# controll.net
KiCad netlist of a schematic drawn in EAGLE
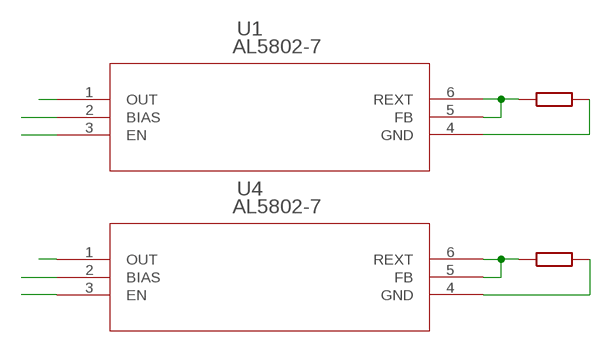
[diagram p0: schematic, sheet 1]
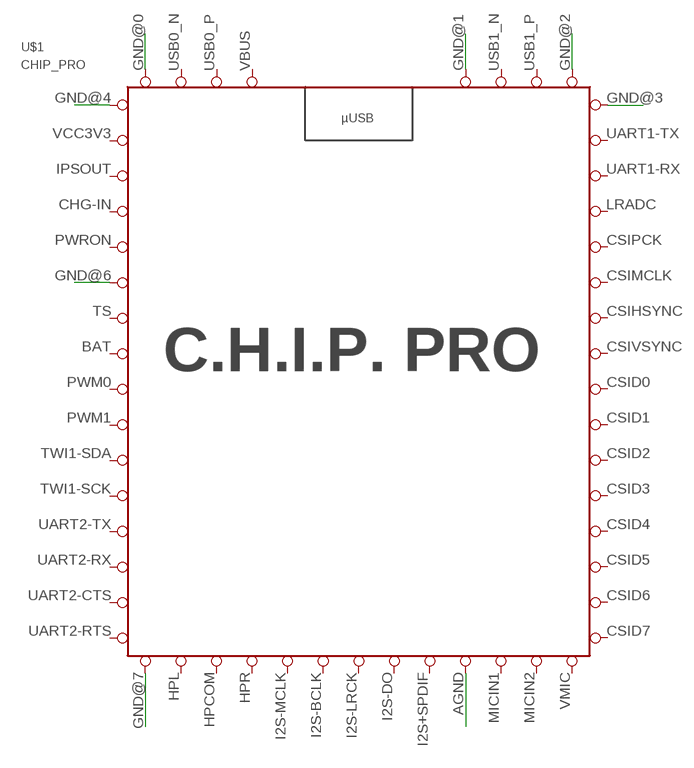
[diagram p1: schematic, sheet 2]
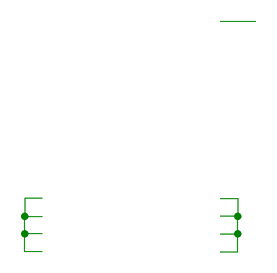
[diagram p2: schematic, sheet 3]

(export (version "E")
  (design (tool "Eeschema 10.0.6"))
  (components
    (comp (ref "U1")
      (value "AL5802-7")
      (footprint "eagle-import:SOT26")
      (fields (field (name "MANUFACTURER_PART_NUMBER") "al58027"))
      (libsource (lib "eagle-import") (part "AL5802-7"))
    )
    (comp (ref "U4")
      (value "AL5802-7")
      (footprint "eagle-import:SOT26")
      (fields (field (name "MANUFACTURER_PART_NUMBER") "al58027"))
      (libsource (lib "eagle-import") (part "AL5802-7"))
    )
    (comp (ref "U$1")
      (value "CHIP_PRO")
      (footprint "eagle-import:CHIP_PRO")
      (libsource (lib "eagle-import") (part "CHIP_PRO"))
    )
  )
  (nets
    (net (code "1") (name "24V") (class "Default")
      (node (ref "U1") (pin "2") (pinfunction "BIAS_2") (pintype "output"))
      (node (ref "U4") (pin "2") (pinfunction "BIAS_2") (pintype "output"))
    )
    (net (code "2") (name "CHG-IN") (class "Default")
      (node (ref "U$1") (pin "CHG-IN") (pinfunction "CHG-IN_CHG-IN") (pintype "power_in"))
    )
    (net (code "3") (name "GND") (class "Default")
      (node (ref "U$1") (pin "AGND") (pinfunction "AGND_AGND") (pintype "power_in"))
      (node (ref "U$1") (pin "GND@0") (pinfunction "GND_GND@0") (pintype "power_in"))
      (node (ref "U$1") (pin "GND@1") (pinfunction "GND_GND@1") (pintype "power_in"))
      (node (ref "U$1") (pin "GND@2") (pinfunction "GND_GND@2") (pintype "power_in"))
      (node (ref "U$1") (pin "GND@3") (pinfunction "GND_GND@3") (pintype "power_in"))
      (node (ref "U$1") (pin "GND@4") (pinfunction "GND_GND@4") (pintype "power_in"))
      (node (ref "U$1") (pin "GND@6") (pinfunction "GND_GND@6") (pintype "power_in"))
      (node (ref "U$1") (pin "GND@7") (pinfunction "GND_GND@7") (pintype "power_in"))
      (node (ref "U1") (pin "4") (pinfunction "GND_4") (pintype "power_in"))
    )
    (net (code "4") (name "IPSOUT") (class "Default")
      (node (ref "U$1") (pin "IPSOUT") (pinfunction "IPSOUT_IPSOUT") (pintype "power_in"))
    )
    (net (code "5") (name "Net-(U1-FB)") (class "Default")
      (node (ref "U1") (pin "5") (pinfunction "FB_5") (pintype "passive"))
      (node (ref "U1") (pin "6") (pinfunction "REXT_6") (pintype "passive"))
    )
    (net (code "6") (name "Net-(U4-FB)") (class "Default")
      (node (ref "U4") (pin "5") (pinfunction "FB_5") (pintype "passive"))
      (node (ref "U4") (pin "6") (pinfunction "REXT_6") (pintype "passive"))
    )
    (net (code "7") (name "VBUS") (class "Default")
      (node (ref "U$1") (pin "VBUS") (pinfunction "VBUS_VBUS") (pintype "power_in"))
    )
    (net (code "8") (name "VCC3V3") (class "Default")
      (node (ref "U$1") (pin "VCC3V3") (pinfunction "VCC3V3_VCC3V3") (pintype "power_in"))
    )
    (net (code "9") (name "unconnected-(U$1-I2SBCLK-PadI2S-BCLK)") (class "Default")
      (node (ref "U$1") (pin "I2S-BCLK") (pinfunction "I2SBCLK_I2S-BCLK") (pintype "bidirectional"))
    )
    (net (code "10") (name "unconnected-(U$1-I2SDO-PadI2S-DO)") (class "Default")
      (node (ref "U$1") (pin "I2S-DO") (pinfunction "I2SDO_I2S-DO") (pintype "bidirectional"))
    )
    (net (code "11") (name "unconnected-(U$1-I2SLRCK-PadI2S-LRCK)") (class "Default")
      (node (ref "U$1") (pin "I2S-LRCK") (pinfunction "I2SLRCK_I2S-LRCK") (pintype "bidirectional"))
    )
    (net (code "12") (name "unconnected-(U$1-I2SMCLK-PadI2S-MCLK)") (class "Default")
      (node (ref "U$1") (pin "I2S-MCLK") (pinfunction "I2SMCLK_I2S-MCLK") (pintype "bidirectional"))
    )
    (net (code "13") (name "unconnected-(U$1-I2SSPDIF-PadI2S+SPDIF)") (class "Default")
      (node (ref "U$1") (pin "I2S+SPDIF") (pinfunction "I2SSPDIF_I2S+SPDIF") (pintype "bidirectional"))
    )
    (net (code "14") (name "unconnected-(U$1-PadBAT)") (class "Default")
      (node (ref "U$1") (pin "BAT") (pinfunction "BAT_BAT") (pintype "bidirectional"))
    )
    (net (code "15") (name "unconnected-(U$1-PadCSID0)") (class "Default")
      (node (ref "U$1") (pin "CSID0") (pinfunction "CSID0_CSID0") (pintype "bidirectional"))
    )
    (net (code "16") (name "unconnected-(U$1-PadCSID1)") (class "Default")
      (node (ref "U$1") (pin "CSID1") (pinfunction "CSID1_CSID1") (pintype "bidirectional"))
    )
    (net (code "17") (name "unconnected-(U$1-PadCSID2)") (class "Default")
      (node (ref "U$1") (pin "CSID2") (pinfunction "CSID2_CSID2") (pintype "bidirectional"))
    )
    (net (code "18") (name "unconnected-(U$1-PadCSID3)") (class "Default")
      (node (ref "U$1") (pin "CSID3") (pinfunction "CSID3_CSID3") (pintype "bidirectional"))
    )
    (net (code "19") (name "unconnected-(U$1-PadCSID4)") (class "Default")
      (node (ref "U$1") (pin "CSID4") (pinfunction "CSID4_CSID4") (pintype "bidirectional"))
    )
    (net (code "20") (name "unconnected-(U$1-PadCSID5)") (class "Default")
      (node (ref "U$1") (pin "CSID5") (pinfunction "CSID5_CSID5") (pintype "bidirectional"))
    )
    (net (code "21") (name "unconnected-(U$1-PadCSID6)") (class "Default")
      (node (ref "U$1") (pin "CSID6") (pinfunction "CSID6_CSID6") (pintype "bidirectional"))
    )
    (net (code "22") (name "unconnected-(U$1-PadCSID7)") (class "Default")
      (node (ref "U$1") (pin "CSID7") (pinfunction "CSID7_CSID7") (pintype "bidirectional"))
    )
    (net (code "23") (name "unconnected-(U$1-PadCSIHSYNC)") (class "Default")
      (node (ref "U$1") (pin "CSIHSYNC") (pinfunction "CSIHSYNC_CSIHSYNC") (pintype "bidirectional"))
    )
    (net (code "24") (name "unconnected-(U$1-PadCSIMCLK)") (class "Default")
      (node (ref "U$1") (pin "CSIMCLK") (pinfunction "CSIMCLK_CSIMCLK") (pintype "bidirectional"))
    )
    (net (code "25") (name "unconnected-(U$1-PadCSIPCK)") (class "Default")
      (node (ref "U$1") (pin "CSIPCK") (pinfunction "CSIPCK_CSIPCK") (pintype "bidirectional"))
    )
    (net (code "26") (name "unconnected-(U$1-PadCSIVSYNC)") (class "Default")
      (node (ref "U$1") (pin "CSIVSYNC") (pinfunction "CSIVSYNC_CSIVSYNC") (pintype "bidirectional"))
    )
    (net (code "27") (name "unconnected-(U$1-PadHPCOM)") (class "Default")
      (node (ref "U$1") (pin "HPCOM") (pinfunction "HPCOM_HPCOM") (pintype "bidirectional"))
    )
    (net (code "28") (name "unconnected-(U$1-PadHPL)") (class "Default")
      (node (ref "U$1") (pin "HPL") (pinfunction "HPL_HPL") (pintype "bidirectional"))
    )
    (net (code "29") (name "unconnected-(U$1-PadHPR)") (class "Default")
      (node (ref "U$1") (pin "HPR") (pinfunction "HPR_HPR") (pintype "bidirectional"))
    )
    (net (code "30") (name "unconnected-(U$1-PadLRADC)") (class "Default")
      (node (ref "U$1") (pin "LRADC") (pinfunction "LRADC_LRADC") (pintype "bidirectional"))
    )
    (net (code "31") (name "unconnected-(U$1-PadMICIN1)") (class "Default")
      (node (ref "U$1") (pin "MICIN1") (pinfunction "MICIN1_MICIN1") (pintype "bidirectional"))
    )
    (net (code "32") (name "unconnected-(U$1-PadMICIN2)") (class "Default")
      (node (ref "U$1") (pin "MICIN2") (pinfunction "MICIN2_MICIN2") (pintype "bidirectional"))
    )
    (net (code "33") (name "unconnected-(U$1-PadPWM0)") (class "Default")
      (node (ref "U$1") (pin "PWM0") (pinfunction "PWM0_PWM0") (pintype "bidirectional"))
    )
    (net (code "34") (name "unconnected-(U$1-PadPWM1)") (class "Default")
      (node (ref "U$1") (pin "PWM1") (pinfunction "PWM1_PWM1") (pintype "bidirectional"))
    )
    (net (code "35") (name "unconnected-(U$1-PadPWRON)") (class "Default")
      (node (ref "U$1") (pin "PWRON") (pinfunction "PWRON_PWRON") (pintype "bidirectional"))
    )
    (net (code "36") (name "unconnected-(U$1-PadTS)") (class "Default")
      (node (ref "U$1") (pin "TS") (pinfunction "TS_TS") (pintype "bidirectional"))
    )
    (net (code "37") (name "unconnected-(U$1-PadTWI1-SCK)") (class "Default")
      (node (ref "U$1") (pin "TWI1-SCK") (pinfunction "TWI1-SCK_TWI1-SCK") (pintype "bidirectional"))
    )
    (net (code "38") (name "unconnected-(U$1-PadTWI1-SDA)") (class "Default")
      (node (ref "U$1") (pin "TWI1-SDA") (pinfunction "TWI1-SDA_TWI1-SDA") (pintype "bidirectional"))
    )
    (net (code "39") (name "unconnected-(U$1-PadUART1-RX)") (class "Default")
      (node (ref "U$1") (pin "UART1-RX") (pinfunction "UART1-RX_UART1-RX") (pintype "bidirectional"))
    )
    (net (code "40") (name "unconnected-(U$1-PadUART1-TX)") (class "Default")
      (node (ref "U$1") (pin "UART1-TX") (pinfunction "UART1-TX_UART1-TX") (pintype "bidirectional"))
    )
    (net (code "41") (name "unconnected-(U$1-PadUART2-CTS)") (class "Default")
      (node (ref "U$1") (pin "UART2-CTS") (pinfunction "UART2-CTS_UART2-CTS") (pintype "bidirectional"))
    )
    (net (code "42") (name "unconnected-(U$1-PadUART2-RTS)") (class "Default")
      (node (ref "U$1") (pin "UART2-RTS") (pinfunction "UART2-RTS_UART2-RTS") (pintype "bidirectional"))
    )
    (net (code "43") (name "unconnected-(U$1-PadUART2-RX)") (class "Default")
      (node (ref "U$1") (pin "UART2-RX") (pinfunction "UART2-RX_UART2-RX") (pintype "bidirectional"))
    )
    (net (code "44") (name "unconnected-(U$1-PadUART2-TX)") (class "Default")
      (node (ref "U$1") (pin "UART2-TX") (pinfunction "UART2-TX_UART2-TX") (pintype "bidirectional"))
    )
    (net (code "45") (name "unconnected-(U$1-PadUSB0_N)") (class "Default")
      (node (ref "U$1") (pin "USB0_N") (pinfunction "USB0_N_USB0_N") (pintype "bidirectional"))
    )
    (net (code "46") (name "unconnected-(U$1-PadUSB0_P)") (class "Default")
      (node (ref "U$1") (pin "USB0_P") (pinfunction "USB0_P_USB0_P") (pintype "bidirectional"))
    )
    (net (code "47") (name "unconnected-(U$1-PadUSB1_N)") (class "Default")
      (node (ref "U$1") (pin "USB1_N") (pinfunction "USB1_N_USB1_N") (pintype "bidirectional"))
    )
    (net (code "48") (name "unconnected-(U$1-PadUSB1_P)") (class "Default")
      (node (ref "U$1") (pin "USB1_P") (pinfunction "USB1_P_USB1_P") (pintype "bidirectional"))
    )
    (net (code "49") (name "unconnected-(U$1-PadVMIC)") (class "Default")
      (node (ref "U$1") (pin "VMIC") (pinfunction "VMIC_VMIC") (pintype "bidirectional"))
    )
    (net (code "50") (name "unconnected-(U1-EN-Pad3)") (class "Default")
      (node (ref "U1") (pin "3") (pinfunction "EN_3") (pintype "passive"))
    )
    (net (code "51") (name "unconnected-(U1-OUT-Pad1)") (class "Default")
      (node (ref "U1") (pin "1") (pinfunction "OUT_1") (pintype "output"))
    )
    (net (code "52") (name "unconnected-(U4-EN-Pad3)") (class "Default")
      (node (ref "U4") (pin "3") (pinfunction "EN_3") (pintype "passive"))
    )
    (net (code "53") (name "unconnected-(U4-GND-Pad4)") (class "Default")
      (node (ref "U4") (pin "4") (pinfunction "GND_4") (pintype "power_in"))
    )
    (net (code "54") (name "unconnected-(U4-OUT-Pad1)") (class "Default")
      (node (ref "U4") (pin "1") (pinfunction "OUT_1") (pintype "output"))
    )
  )
)
